# UC3842_SMPS_12V_5A_V2.net
KiCad netlist of a schematic drawn in Altium Designer
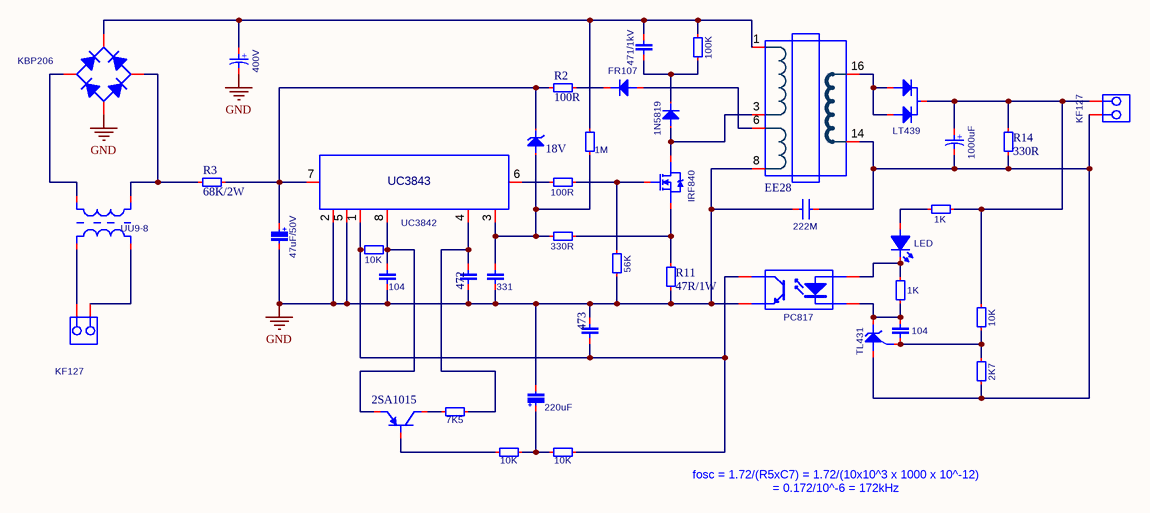
[diagram p0: UC3842_SMPS_12V_5A_V2.SchDoc]

(export (version "E")
  (design (tool "Eeschema 10.0.6"))
  (components
    (comp (ref "C1")
      (value "47uF/50V")
      (footprint "CAP_RAD_2.5mm")
      (libsource (lib "MyAltiumLibrary") (part "Capacitor(Radian)"))
    )
    (comp (ref "C2")
      (value "400V")
      (footprint "CAP_RAD_D12.5x15_POL_BK")
      (libsource (lib "") (part "Capacitor(Radian)_2"))
    )
    (comp (ref "C3")
      (value "471/1kV")
      (footprint "CAP_DISC_4x3_YL")
      (libsource (lib "") (part "Capacitors(Disc)_1"))
    )
    (comp (ref "C4")
      (value "1000uF")
      (footprint "CAP_RAD_D10x12.5_POL_BK")
      (libsource (lib "") (part "Capacitor(Radian)_2"))
    )
    (comp (ref "C5")
      (value "222M")
      (footprint "CAP_DISC_Y2222")
      (libsource (lib "") (part "Capacitors(Disc)_2"))
    )
    (comp (ref "C6")
      (value "104")
      (footprint "CAP_Ceramic_Disc_2")
      (libsource (lib "") (part "Capacitors(Disc)_1"))
    )
    (comp (ref "C7")
      (value "472")
      (footprint "CAP_DISC_4x3_YL")
      (libsource (lib "MyAltiumLibrary") (part "Capacitors(Disc)"))
    )
    (comp (ref "C8")
      (value "331")
      (footprint "CAP_DISC_4x3_YL")
      (libsource (lib "") (part "Capacitors(Disc)_1"))
    )
    (comp (ref "C9")
      (value "104")
      (footprint "CAP_DISC_4x3_YL")
      (libsource (lib "MyAltiumLibrary") (part "Capacitors(Disc)"))
    )
    (comp (ref "C10")
      (value "473")
      (footprint "CAP_DISC_4x3_YL")
      (libsource (lib "MyAltiumLibrary") (part "Capacitors(Disc)"))
    )
    (comp (ref "C11")
      (value "220uF")
      (footprint "CAP_RAD_2.5mm")
      (libsource (lib "") (part "Capacitor(Radian)_1"))
    )
    (comp (ref "D1")
      (value "LT439")
      (footprint "TO-220-HEAT-SINK-1")
      (libsource (lib "MyAltiumLibrary") (part "Diode-LT439"))
    )
    (comp (ref "D2")
      (value "KBP206")
      (footprint "DIODE-KBP206")
      (libsource (lib "MyAltiumLibrary") (part "Diode-KBP206"))
    )
    (comp (ref "D3")
      (value "18V")
      (footprint "DO-204AL-RD")
      (libsource (lib "MyAltiumLibrary") (part "Diode-Zener"))
    )
    (comp (ref "D4")
      (value "1N5819")
      (footprint "DO-204AL-BK")
      (description "1A - Schotky Diode")
      (libsource (lib "MyAltiumLibrary") (part "Diode-1N5819"))
    )
    (comp (ref "D7")
      (value "LED")
      (footprint "LED_3MM_GREEN")
      (libsource (lib "MyAltiumLibrary") (part "LED 3MM"))
    )
    (comp (ref "D8")
      (value "FR107")
      (footprint "DO-204AL-BK")
      (description "1A - Schotky Diode")
      (libsource (lib "") (part "Diode-1N5819_1"))
    )
    (comp (ref "IC1")
      (value "UC3842")
      (footprint "DIP-8")
      (libsource (lib "MyAltiumLibrary") (part "SMPS-UC3842"))
    )
    (comp (ref "J1")
      (value "KF127")
      (footprint "DG127-5.0-02P-14-00AH")
      (libsource (lib "MyAltiumLibrary") (part "DG127-5.0-02P-14-00AH"))
    )
    (comp (ref "J2")
      (value "KF127")
      (footprint "DG127-5.0-02P-14-00AH")
      (libsource (lib "") (part "DG127-5.0-02P-14-00AH_1"))
    )
    (comp (ref "Q1")
      (value "IRF840")
      (footprint "TO-220-HEAT-SINK-1")
      (libsource (lib "MyAltiumLibrary") (part "Mosfet-IRF840"))
    )
    (comp (ref "Q2")
      (value "2SA1015")
      (footprint "TO-92")
      (libsource (lib "MyAltiumLibrary") (part "Transistor-2SA1015 (TO-92)"))
    )
    (comp (ref "R1")
      (value "100K")
      (footprint "RES-0.25W-H-CF")
      (libsource (lib "MyAltiumLibrary") (part "Resistors THD"))
    )
    (comp (ref "R2") (value "100R") (footprint "RES-0.5W-H") (libsource (lib "") (part "Resistors THD_2")))
    (comp (ref "R3") (value "68K/2W") (footprint "RES-2W-H") (libsource (lib "") (part "Resistors THD_2")))
    (comp (ref "R4") (value "1K") (footprint "RES-0.25W-H-CF") (libsource (lib "") (part "Resistors THD_3")))
    (comp (ref "R5") (value "7K5") (footprint "RES-0.25W-H-CF") (libsource (lib "") (part "Resistors THD_3")))
    (comp (ref "R6")
      (value "100R")
      (footprint "RES-0.25W-H-CF")
      (libsource (lib "") (part "Resistors THD_2"))
    )
    (comp (ref "R7") (value "1K") (footprint "RES-0.25W-V-CF") (libsource (lib "") (part "Resistors THD_1")))
    (comp (ref "R8")
      (value "330R")
      (footprint "RES-0.25W-H-CF")
      (libsource (lib "") (part "Resistors THD_2"))
    )
    (comp (ref "R9") (value "10K") (footprint "RES-0.25W-H-CF") (libsource (lib "") (part "Resistors THD_1")))
    (comp (ref "R10")
      (value "56K")
      (footprint "RES-0.25W-H-CF")
      (libsource (lib "MyAltiumLibrary") (part "Resistors THD"))
    )
    (comp (ref "R11")
      (value "47R/1W")
      (footprint "RES-1W-H")
      (libsource (lib "MyAltiumLibrary") (part "Resistors THD"))
    )
    (comp (ref "R12")
      (value "2K7")
      (footprint "RES-0.25W-H-CF")
      (libsource (lib "") (part "Resistors THD_1"))
    )
    (comp (ref "R13") (value "1M") (footprint "RES-0.25W-H-CF") (libsource (lib "") (part "Resistors THD_1")))
    (comp (ref "R14")
      (value "330R")
      (footprint "RES-1W-V")
      (libsource (lib "MyAltiumLibrary") (part "Resistors THD"))
    )
    (comp (ref "R15")
      (value "10K")
      (footprint "RES-0.25W-H-CF")
      (libsource (lib "") (part "Resistors THD_2"))
    )
    (comp (ref "R16")
      (value "10K")
      (footprint "RES-0.25W-H-CF")
      (libsource (lib "") (part "Resistors THD_3"))
    )
    (comp (ref "R17")
      (value "10K")
      (footprint "RES-0.25W-H-CF")
      (libsource (lib "") (part "Resistors THD_3"))
    )
    (comp (ref "T1")
      (value "EE28")
      (footprint "TRANSFORMER-EE28-VERTICAL(8+8)")
      (libsource (lib "MyAltiumLibrary") (part "TRANS-EE28-13-7-VERTICAL(8+8)"))
    )
    (comp (ref "T2")
      (value "UU9-8")
      (footprint "INDUCTOR-BOBBIN-UF9-8")
      (libsource (lib "MyAltiumLibrary") (part "Inductor-UU9-8"))
    )
    (comp (ref "U1")
      (value "PC817")
      (footprint "PC817-DIP")
      (libsource (lib "MyAltiumLibrary") (part "Opto-PC817"))
    )
    (comp (ref "U2")
      (value "TL431")
      (footprint "TO-92")
      (libsource (lib "MyAltiumLibrary") (part "Ic-TL431"))
    )
  )
  (nets
    (net (code "1") (name "GND") (class "Default")
      (node (ref "C1") (pin "2") (pinfunction "2_2") (pintype "passive"))
      (node (ref "C10") (pin "2") (pinfunction "2_2") (pintype "passive"))
      (node (ref "C11") (pin "2") (pinfunction "2_2") (pintype "passive"))
      (node (ref "C2") (pin "2") (pinfunction "2_2") (pintype "passive"))
      (node (ref "C5") (pin "1") (pinfunction "1_1") (pintype "passive"))
      (node (ref "C6") (pin "2") (pinfunction "2_2") (pintype "passive"))
      (node (ref "C7") (pin "1") (pinfunction "1_1") (pintype "passive"))
      (node (ref "C8") (pin "2") (pinfunction "2_2") (pintype "passive"))
      (node (ref "D2") (pin "4") (pinfunction "-_4") (pintype "passive"))
      (node (ref "IC1") (pin "2") (pinfunction "VFB_2") (pintype "passive"))
      (node (ref "IC1") (pin "5") (pinfunction "GND_5") (pintype "passive"))
      (node (ref "R10") (pin "1") (pinfunction "1_1") (pintype "passive"))
      (node (ref "R11") (pin "1") (pinfunction "1_1") (pintype "passive"))
      (node (ref "T1") (pin "8") (pinfunction "8_8") (pintype "passive"))
      (node (ref "U1") (pin "3") (pinfunction "E_3") (pintype "passive"))
    )
    (net (code "2") (name "Net-(C3-Pad2)") (class "Default")
      (node (ref "C3") (pin "2") (pinfunction "2_2") (pintype "passive"))
      (node (ref "D4") (pin "2") (pinfunction "2_2") (pintype "passive"))
      (node (ref "R1") (pin "1") (pinfunction "1_1") (pintype "passive"))
    )
    (net (code "3") (name "Net-(C4-Pad1)") (class "Default")
      (node (ref "C4") (pin "1") (pinfunction "1_1") (pintype "passive"))
      (node (ref "D1") (pin "2") (pinfunction "2_2") (pintype "passive"))
      (node (ref "J2") (pin "2") (pinfunction "2_2") (pintype "passive"))
      (node (ref "R14") (pin "2") (pinfunction "2_2") (pintype "passive"))
      (node (ref "R4") (pin "1") (pinfunction "1_1") (pintype "passive"))
      (node (ref "R9") (pin "1") (pinfunction "1_1") (pintype "passive"))
    )
    (net (code "4") (name "Net-(C4-Pad2)") (class "Default")
      (node (ref "C4") (pin "2") (pinfunction "2_2") (pintype "passive"))
      (node (ref "C5") (pin "2") (pinfunction "2_2") (pintype "passive"))
      (node (ref "J2") (pin "1") (pinfunction "1_1") (pintype "passive"))
      (node (ref "R12") (pin "2") (pinfunction "2_2") (pintype "passive"))
      (node (ref "R14") (pin "1") (pinfunction "1_1") (pintype "passive"))
      (node (ref "T1") (pin "14") (pinfunction "14_14") (pintype "passive"))
      (node (ref "U2") (pin "2") (pinfunction "2_2") (pintype "passive"))
    )
    (net (code "5") (name "Net-(C9-Pad1)") (class "Default")
      (node (ref "C9") (pin "1") (pinfunction "1_1") (pintype "passive"))
      (node (ref "R12") (pin "1") (pinfunction "1_1") (pintype "passive"))
      (node (ref "R9") (pin "2") (pinfunction "2_2") (pintype "passive"))
      (node (ref "U2") (pin "1") (pinfunction "1_1") (pintype "passive"))
    )
    (net (code "6") (name "Net-(C11-Pad1)") (class "Default")
      (node (ref "C11") (pin "1") (pinfunction "1_1") (pintype "passive"))
      (node (ref "R16") (pin "1") (pinfunction "1_1") (pintype "passive"))
      (node (ref "R17") (pin "2") (pinfunction "2_2") (pintype "passive"))
    )
    (net (code "7") (name "Net-(D1-Pad1)") (class "Default")
      (node (ref "D1") (pin "1") (pinfunction "1_1") (pintype "passive"))
      (node (ref "D1") (pin "3") (pinfunction "3_3") (pintype "passive"))
      (node (ref "T1") (pin "16") (pinfunction "16_16") (pintype "passive"))
    )
    (net (code "8") (name "Net-(D2-+)") (class "Default")
      (node (ref "C2") (pin "1") (pinfunction "1_1") (pintype "passive"))
      (node (ref "C3") (pin "1") (pinfunction "1_1") (pintype "passive"))
      (node (ref "D2") (pin "1") (pinfunction "+_1") (pintype "passive"))
      (node (ref "R1") (pin "2") (pinfunction "2_2") (pintype "passive"))
      (node (ref "R13") (pin "1") (pinfunction "1_1") (pintype "passive"))
      (node (ref "T1") (pin "1") (pinfunction "1_1") (pintype "passive"))
    )
    (net (code "9") (name "Net-(D2-AC-Pad2)") (class "Default")
      (node (ref "D2") (pin "2") (pinfunction "AC_2") (pintype "passive"))
      (node (ref "T2") (pin "2") (pinfunction "4_2") (pintype "passive"))
    )
    (net (code "10") (name "Net-(D2-AC-Pad3)") (class "Default")
      (node (ref "D2") (pin "3") (pinfunction "AC_3") (pintype "passive"))
      (node (ref "R3") (pin "1") (pinfunction "1_1") (pintype "passive"))
      (node (ref "T2") (pin "4") (pinfunction "4_4") (pintype "passive"))
    )
    (net (code "11") (name "Net-(D7-A)") (class "Default")
      (node (ref "D7") (pin "1") (pinfunction "A_1") (pintype "passive"))
      (node (ref "R4") (pin "2") (pinfunction "2_2") (pintype "passive"))
    )
    (net (code "12") (name "Net-(D7-K)") (class "Default")
      (node (ref "D7") (pin "2") (pinfunction "K_2") (pintype "passive"))
      (node (ref "R7") (pin "1") (pinfunction "1_1") (pintype "passive"))
      (node (ref "U1") (pin "1") (pinfunction "A_1") (pintype "passive"))
    )
    (net (code "13") (name "Net-(D8-Pad1)") (class "Default")
      (node (ref "D8") (pin "1") (pinfunction "1_1") (pintype "passive"))
      (node (ref "T1") (pin "6") (pinfunction "6_6") (pintype "passive"))
    )
    (net (code "14") (name "Net-(D8-Pad2)") (class "Default")
      (node (ref "D8") (pin "2") (pinfunction "2_2") (pintype "passive"))
      (node (ref "R2") (pin "2") (pinfunction "2_2") (pintype "passive"))
    )
    (net (code "15") (name "Net-(IC1-COMP)") (class "Default")
      (node (ref "C10") (pin "1") (pinfunction "1_1") (pintype "passive"))
      (node (ref "IC1") (pin "1") (pinfunction "COMP_1") (pintype "passive"))
      (node (ref "R15") (pin "1") (pinfunction "1_1") (pintype "passive"))
      (node (ref "R17") (pin "1") (pinfunction "1_1") (pintype "passive"))
      (node (ref "U1") (pin "4") (pinfunction "C_4") (pintype "passive"))
    )
    (net (code "16") (name "Net-(IC1-CS)") (class "Default")
      (node (ref "C8") (pin "1") (pinfunction "1_1") (pintype "passive"))
      (node (ref "D3") (pin "1") (pinfunction "1_1") (pintype "passive"))
      (node (ref "IC1") (pin "3") (pinfunction "CS_3") (pintype "passive"))
      (node (ref "R13") (pin "2") (pinfunction "2_2") (pintype "passive"))
      (node (ref "R8") (pin "1") (pinfunction "1_1") (pintype "passive"))
    )
    (net (code "17") (name "Net-(IC1-OUT)") (class "Default")
      (node (ref "IC1") (pin "6") (pinfunction "OUT_6") (pintype "passive"))
      (node (ref "R6") (pin "1") (pinfunction "1_1") (pintype "passive"))
    )
    (net (code "18") (name "Net-(IC1-RT{slash}CT)") (class "Default")
      (node (ref "C7") (pin "2") (pinfunction "2_2") (pintype "passive"))
      (node (ref "IC1") (pin "4") (pinfunction "RT/CT_4") (pintype "passive"))
      (node (ref "R5") (pin "1") (pinfunction "1_1") (pintype "passive"))
    )
    (net (code "19") (name "Net-(IC1-VCC)") (class "Default")
      (node (ref "C1") (pin "1") (pinfunction "1_1") (pintype "passive"))
      (node (ref "D3") (pin "2") (pinfunction "2_2") (pintype "passive"))
      (node (ref "IC1") (pin "7") (pinfunction "VCC_7") (pintype "passive"))
      (node (ref "R2") (pin "1") (pinfunction "1_1") (pintype "passive"))
      (node (ref "R3") (pin "2") (pinfunction "2_2") (pintype "passive"))
    )
    (net (code "20") (name "Net-(IC1-VREF)") (class "Default")
      (node (ref "C6") (pin "1") (pinfunction "1_1") (pintype "passive"))
      (node (ref "IC1") (pin "8") (pinfunction "VREF_8") (pintype "passive"))
      (node (ref "Q2") (pin "1") (pinfunction "E_1") (pintype "passive"))
      (node (ref "R15") (pin "2") (pinfunction "2_2") (pintype "passive"))
    )
    (net (code "21") (name "Net-(J1-Pad1)") (class "Default")
      (node (ref "J1") (pin "1") (pinfunction "1_1") (pintype "passive"))
      (node (ref "T2") (pin "1") (pinfunction "1_1") (pintype "passive"))
    )
    (net (code "22") (name "Net-(J1-Pad2)") (class "Default")
      (node (ref "J1") (pin "2") (pinfunction "2_2") (pintype "passive"))
      (node (ref "T2") (pin "3") (pinfunction "3_3") (pintype "passive"))
    )
    (net (code "23") (name "Net-(Q1-D)") (class "Default")
      (node (ref "D4") (pin "1") (pinfunction "1_1") (pintype "passive"))
      (node (ref "Q1") (pin "2") (pinfunction "D_2") (pintype "passive"))
      (node (ref "T1") (pin "3") (pinfunction "3_3") (pintype "passive"))
    )
    (net (code "24") (name "Net-(Q1-G)") (class "Default")
      (node (ref "Q1") (pin "1") (pinfunction "G_1") (pintype "passive"))
      (node (ref "R10") (pin "2") (pinfunction "2_2") (pintype "passive"))
      (node (ref "R6") (pin "2") (pinfunction "2_2") (pintype "passive"))
    )
    (net (code "25") (name "Net-(Q1-S)") (class "Default")
      (node (ref "Q1") (pin "3") (pinfunction "S_3") (pintype "passive"))
      (node (ref "R11") (pin "2") (pinfunction "2_2") (pintype "passive"))
      (node (ref "R8") (pin "2") (pinfunction "2_2") (pintype "passive"))
    )
    (net (code "26") (name "Net-(Q2-B)") (class "Default")
      (node (ref "Q2") (pin "3") (pinfunction "B_3") (pintype "passive"))
      (node (ref "R16") (pin "2") (pinfunction "2_2") (pintype "passive"))
    )
    (net (code "27") (name "Net-(Q2-C)") (class "Default")
      (node (ref "Q2") (pin "2") (pinfunction "C_2") (pintype "passive"))
      (node (ref "R5") (pin "2") (pinfunction "2_2") (pintype "passive"))
    )
    (net (code "28") (name "Net-(U1-K)") (class "Default")
      (node (ref "C9") (pin "2") (pinfunction "2_2") (pintype "passive"))
      (node (ref "R7") (pin "2") (pinfunction "2_2") (pintype "passive"))
      (node (ref "U1") (pin "2") (pinfunction "K_2") (pintype "passive"))
      (node (ref "U2") (pin "3") (pinfunction "3_3") (pintype "passive"))
    )
  )
)
